# emoteino.net
KiCad netlist of a schematic drawn in EAGLE
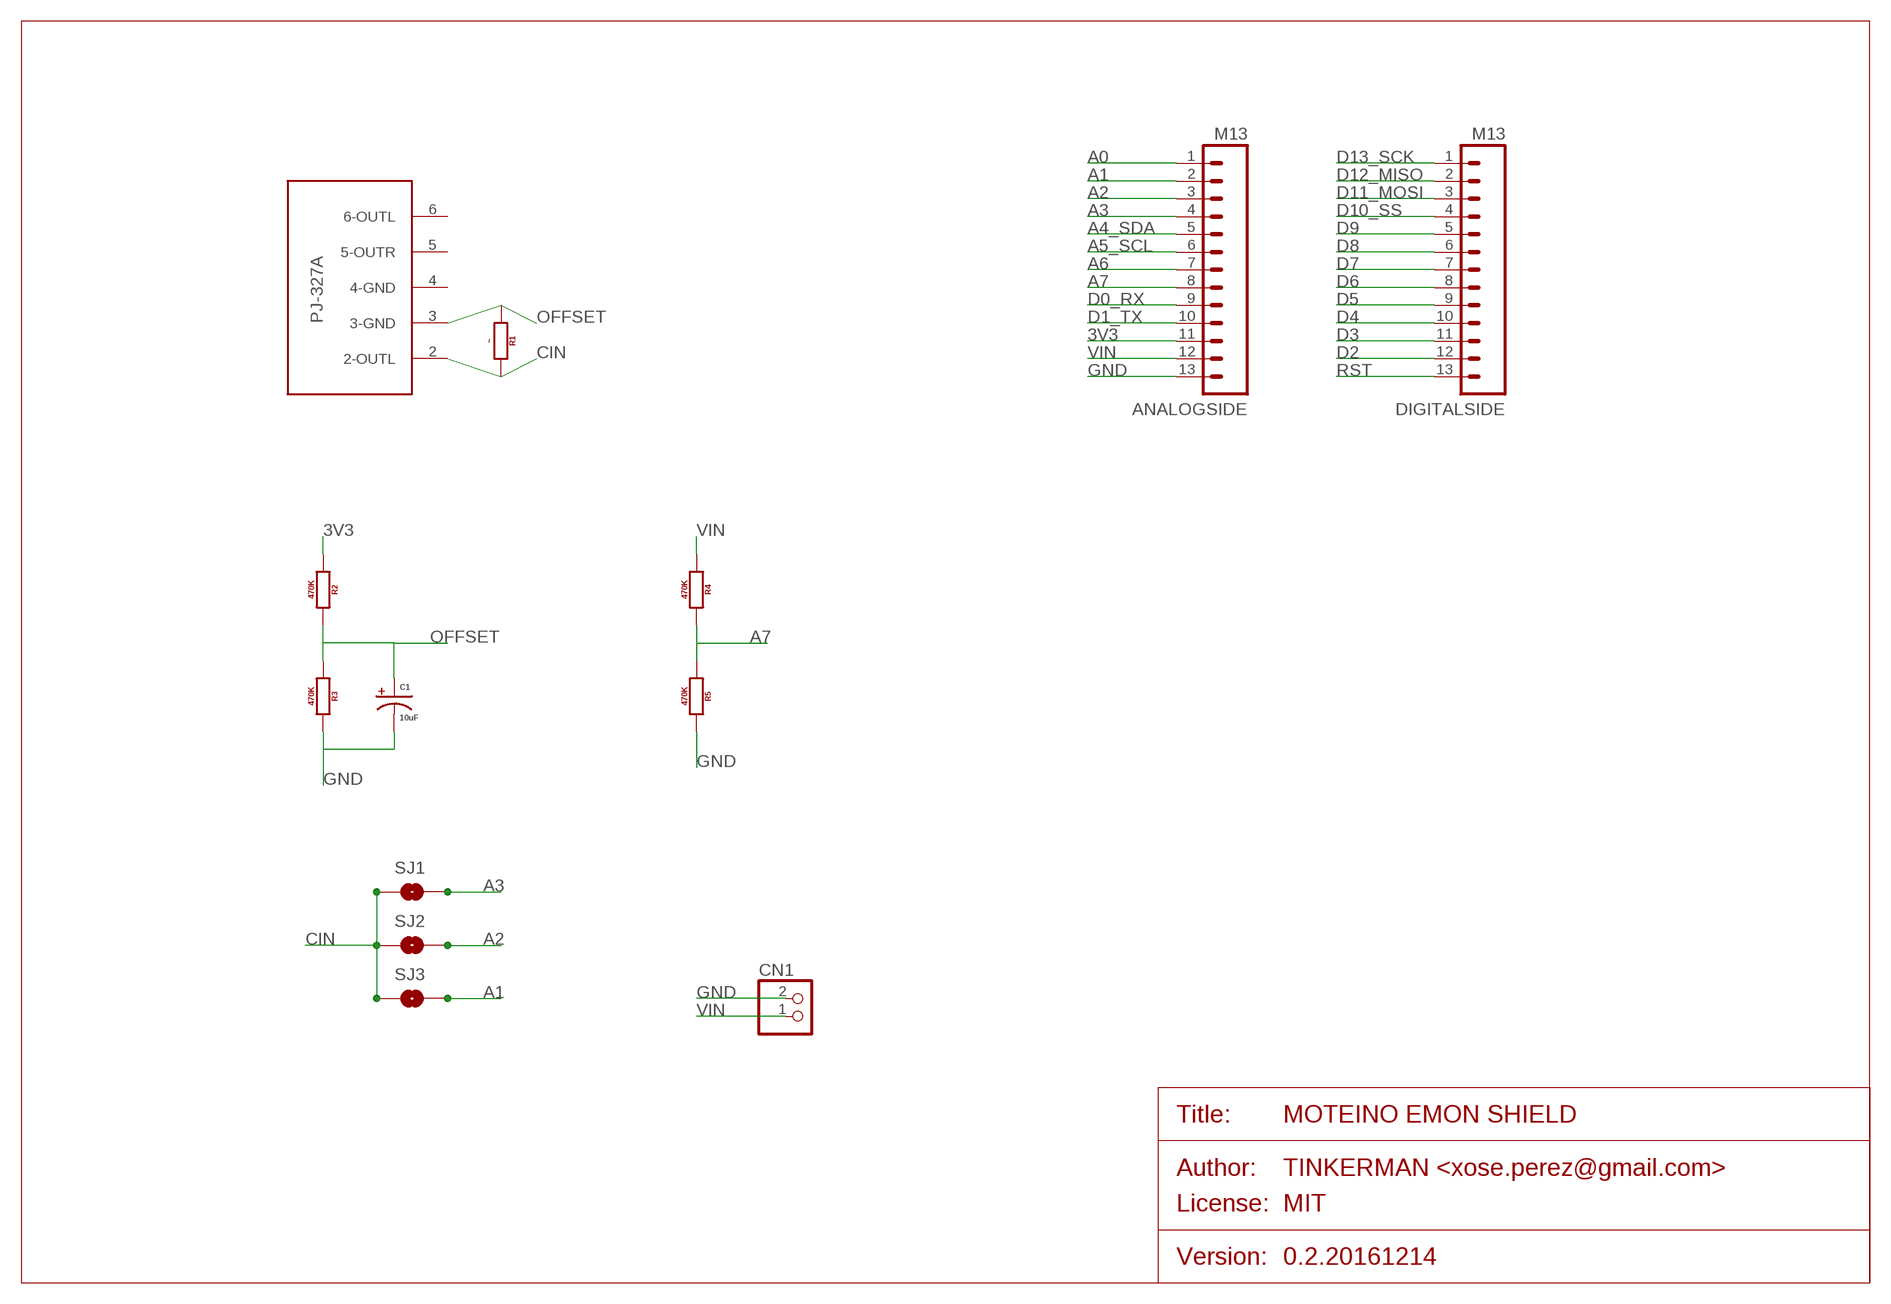
[diagram p0: schematic, sheet 1]

(export (version "E")
  (design (tool "Eeschema 10.0.6"))
  (components
    (comp (ref "ANALOGSIDE")
      (value "M13")
      (footprint "eagle-import:1X13_NO_SILK")
      (libsource (lib "eagle-import") (part "M13"))
    )
    (comp (ref "C1")
      (value "10uF")
      (footprint "eagle-import:CPOL-RADIAL-10UF-25V")
      (libsource (lib "eagle-import") (part "CAP_POLPTH2"))
    )
    (comp (ref "CN1")
      (value "JST_2PIN-SMT-RA")
      (footprint "eagle-import:JST-PH-2-SMT-RA")
      (libsource (lib "eagle-import") (part "JST_2PIN-SMT-RA"))
    )
    (comp (ref "CURR1")
      (value "PJ-327A")
      (footprint "eagle-import:PJ-327A")
      (libsource (lib "eagle-import") (part "PJ-327A"))
    )
    (comp (ref "DIGITALSIDE")
      (value "M13")
      (footprint "eagle-import:1X13_NO_SILK")
      (libsource (lib "eagle-import") (part "M13"))
    )
    (comp (ref "R1")
      (value "~")
      (footprint "eagle-import:0805")
      (libsource (lib "eagle-import") (part "RESISTOR0805"))
    )
    (comp (ref "R2")
      (value "470K")
      (footprint "eagle-import:0805")
      (libsource (lib "eagle-import") (part "RESISTOR0805"))
    )
    (comp (ref "R3")
      (value "470K")
      (footprint "eagle-import:0805")
      (libsource (lib "eagle-import") (part "RESISTOR0805"))
    )
    (comp (ref "R4")
      (value "470K")
      (footprint "eagle-import:0805")
      (libsource (lib "eagle-import") (part "RESISTOR0805"))
    )
    (comp (ref "R5")
      (value "470K")
      (footprint "eagle-import:0805")
      (libsource (lib "eagle-import") (part "RESISTOR0805"))
    )
    (comp (ref "SJ1")
      (value "SOLDERJUMPERNO")
      (footprint "eagle-import:SJ_2S-NO")
      (libsource (lib "eagle-import") (part "SOLDERJUMPERNO"))
    )
    (comp (ref "SJ2")
      (value "SOLDERJUMPERNO")
      (footprint "eagle-import:SJ_2S-NO")
      (libsource (lib "eagle-import") (part "SOLDERJUMPERNO"))
    )
    (comp (ref "SJ3")
      (value "SOLDERJUMPERNO")
      (footprint "eagle-import:SJ_2S-NO")
      (libsource (lib "eagle-import") (part "SOLDERJUMPERNO"))
    )
  )
  (nets
    (net (code "1") (name "/3V3") (class "Default")
      (node (ref "ANALOGSIDE") (pin "11") (pinfunction "11_11") (pintype "passive"))
      (node (ref "R2") (pin "1") (pinfunction "1_1") (pintype "passive"))
    )
    (net (code "2") (name "/A0") (class "Default")
      (node (ref "ANALOGSIDE") (pin "1") (pinfunction "1_1") (pintype "passive"))
    )
    (net (code "3") (name "/A1") (class "Default")
      (node (ref "ANALOGSIDE") (pin "2") (pinfunction "2_2") (pintype "passive"))
      (node (ref "SJ3") (pin "2") (pinfunction "2_2") (pintype "passive"))
    )
    (net (code "4") (name "/A2") (class "Default")
      (node (ref "ANALOGSIDE") (pin "3") (pinfunction "3_3") (pintype "passive"))
      (node (ref "SJ2") (pin "2") (pinfunction "2_2") (pintype "passive"))
    )
    (net (code "5") (name "/A3") (class "Default")
      (node (ref "ANALOGSIDE") (pin "4") (pinfunction "4_4") (pintype "passive"))
      (node (ref "SJ1") (pin "2") (pinfunction "2_2") (pintype "passive"))
    )
    (net (code "6") (name "/A4_SDA") (class "Default")
      (node (ref "ANALOGSIDE") (pin "5") (pinfunction "5_5") (pintype "passive"))
    )
    (net (code "7") (name "/A5_SCL") (class "Default")
      (node (ref "ANALOGSIDE") (pin "6") (pinfunction "6_6") (pintype "passive"))
    )
    (net (code "8") (name "/A6") (class "Default")
      (node (ref "ANALOGSIDE") (pin "7") (pinfunction "7_7") (pintype "passive"))
    )
    (net (code "9") (name "/A7") (class "Default")
      (node (ref "ANALOGSIDE") (pin "8") (pinfunction "8_8") (pintype "passive"))
      (node (ref "R4") (pin "2") (pinfunction "2_2") (pintype "passive"))
      (node (ref "R5") (pin "1") (pinfunction "1_1") (pintype "passive"))
    )
    (net (code "10") (name "/CIN") (class "Default")
      (node (ref "CURR1") (pin "2") (pinfunction "2-OUTL_2") (pintype "bidirectional"))
      (node (ref "R1") (pin "2") (pinfunction "2_2") (pintype "passive"))
      (node (ref "SJ1") (pin "1") (pinfunction "1_1") (pintype "passive"))
      (node (ref "SJ2") (pin "1") (pinfunction "1_1") (pintype "passive"))
      (node (ref "SJ3") (pin "1") (pinfunction "1_1") (pintype "passive"))
    )
    (net (code "11") (name "/D0_RX") (class "Default")
      (node (ref "ANALOGSIDE") (pin "9") (pinfunction "9_9") (pintype "passive"))
    )
    (net (code "12") (name "/D1_TX") (class "Default")
      (node (ref "ANALOGSIDE") (pin "10") (pinfunction "10_10") (pintype "passive"))
    )
    (net (code "13") (name "/D2") (class "Default")
      (node (ref "DIGITALSIDE") (pin "12") (pinfunction "12_12") (pintype "passive"))
    )
    (net (code "14") (name "/D3") (class "Default")
      (node (ref "DIGITALSIDE") (pin "11") (pinfunction "11_11") (pintype "passive"))
    )
    (net (code "15") (name "/D4") (class "Default")
      (node (ref "DIGITALSIDE") (pin "10") (pinfunction "10_10") (pintype "passive"))
    )
    (net (code "16") (name "/D5") (class "Default")
      (node (ref "DIGITALSIDE") (pin "9") (pinfunction "9_9") (pintype "passive"))
    )
    (net (code "17") (name "/D6") (class "Default")
      (node (ref "DIGITALSIDE") (pin "8") (pinfunction "8_8") (pintype "passive"))
    )
    (net (code "18") (name "/D7") (class "Default")
      (node (ref "DIGITALSIDE") (pin "7") (pinfunction "7_7") (pintype "passive"))
    )
    (net (code "19") (name "/D8") (class "Default")
      (node (ref "DIGITALSIDE") (pin "6") (pinfunction "6_6") (pintype "passive"))
    )
    (net (code "20") (name "/D9") (class "Default")
      (node (ref "DIGITALSIDE") (pin "5") (pinfunction "5_5") (pintype "passive"))
    )
    (net (code "21") (name "/D10_SS") (class "Default")
      (node (ref "DIGITALSIDE") (pin "4") (pinfunction "4_4") (pintype "passive"))
    )
    (net (code "22") (name "/D11_MOSI") (class "Default")
      (node (ref "DIGITALSIDE") (pin "3") (pinfunction "3_3") (pintype "passive"))
    )
    (net (code "23") (name "/D12_MISO") (class "Default")
      (node (ref "DIGITALSIDE") (pin "2") (pinfunction "2_2") (pintype "passive"))
    )
    (net (code "24") (name "/D13_SCK") (class "Default")
      (node (ref "DIGITALSIDE") (pin "1") (pinfunction "1_1") (pintype "passive"))
    )
    (net (code "25") (name "/GND") (class "Default")
      (node (ref "ANALOGSIDE") (pin "13") (pinfunction "13_13") (pintype "passive"))
      (node (ref "C1") (pin "2") (pinfunction "-_2") (pintype "passive"))
      (node (ref "CN1") (pin "2") (pinfunction "1_2") (pintype "passive"))
      (node (ref "R3") (pin "2") (pinfunction "2_2") (pintype "passive"))
      (node (ref "R5") (pin "2") (pinfunction "2_2") (pintype "passive"))
    )
    (net (code "26") (name "/OFFSET") (class "Default")
      (node (ref "C1") (pin "1") (pinfunction "+_1") (pintype "passive"))
      (node (ref "CURR1") (pin "3") (pinfunction "3-GND_3") (pintype "bidirectional"))
      (node (ref "R1") (pin "1") (pinfunction "1_1") (pintype "passive"))
      (node (ref "R2") (pin "2") (pinfunction "2_2") (pintype "passive"))
      (node (ref "R3") (pin "1") (pinfunction "1_1") (pintype "passive"))
    )
    (net (code "27") (name "/RST") (class "Default")
      (node (ref "DIGITALSIDE") (pin "13") (pinfunction "13_13") (pintype "passive"))
    )
    (net (code "28") (name "/VIN") (class "Default")
      (node (ref "ANALOGSIDE") (pin "12") (pinfunction "12_12") (pintype "passive"))
      (node (ref "CN1") (pin "1") (pinfunction "2_1") (pintype "passive"))
      (node (ref "R4") (pin "1") (pinfunction "1_1") (pintype "passive"))
    )
    (net (code "29") (name "unconnected-(CURR1-4-GND-Pad4)") (class "Default")
      (node (ref "CURR1") (pin "4") (pinfunction "4-GND_4") (pintype "bidirectional"))
    )
    (net (code "30") (name "unconnected-(CURR1-5-OUTR-Pad5)") (class "Default")
      (node (ref "CURR1") (pin "5") (pinfunction "5-OUTR_5") (pintype "bidirectional"))
    )
    (net (code "31") (name "unconnected-(CURR1-6-OUTL-Pad6)") (class "Default")
      (node (ref "CURR1") (pin "6") (pinfunction "6-OUTL_6") (pintype "bidirectional"))
    )
  )
)
